# PowerSection.net
KiCad netlist of a schematic drawn in EAGLE
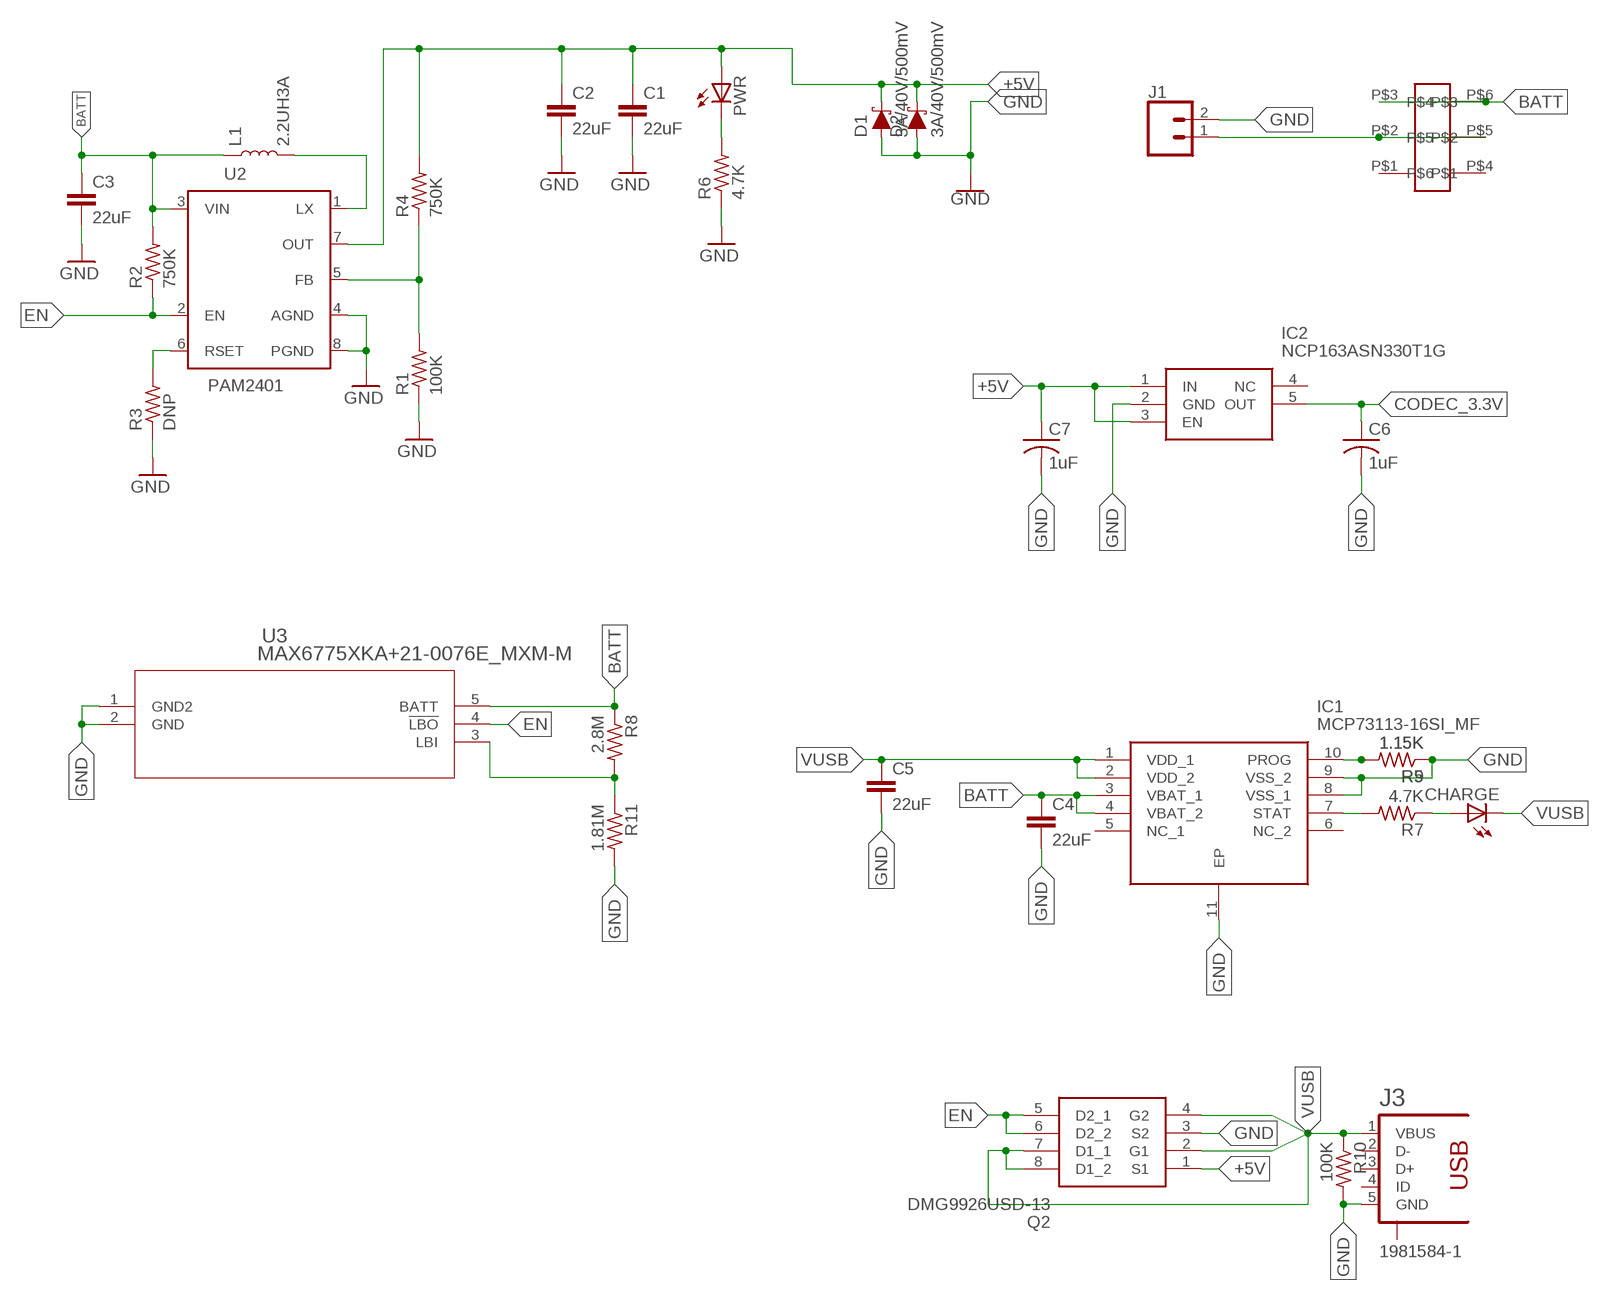
[diagram p0: schematic, sheet 1]

(export (version "E")
  (design (tool "Eeschema 10.0.6"))
  (components
    (comp (ref "C1")
      (value "22uF")
      (footprint "eagle-import:0805")
      (libsource (lib "eagle-import") (part "22UF-0805-6.3V-20%"))
    )
    (comp (ref "C2")
      (value "22uF")
      (footprint "eagle-import:0805")
      (libsource (lib "eagle-import") (part "22UF-0805-6.3V-20%"))
    )
    (comp (ref "C3")
      (value "22uF")
      (footprint "eagle-import:0805")
      (libsource (lib "eagle-import") (part "22UF-0805-6.3V-20%"))
    )
    (comp (ref "C4")
      (value "22uF")
      (footprint "eagle-import:0805")
      (libsource (lib "eagle-import") (part "22UF-0805-6.3V-20%"))
    )
    (comp (ref "C5")
      (value "22uF")
      (footprint "eagle-import:0805")
      (libsource (lib "eagle-import") (part "22UF-0805-6.3V-20%"))
    )
    (comp (ref "C6")
      (value "1uF")
      (footprint "eagle-import:C1206")
      (libsource (lib "eagle-import") (part "C-USC1206"))
    )
    (comp (ref "C7")
      (value "1uF")
      (footprint "eagle-import:C1206")
      (libsource (lib "eagle-import") (part "C-USC1206"))
    )
    (comp (ref "CHARGE")
      (value "LEDCHIPLED_0805")
      (footprint "eagle-import:CHIPLED_0805")
      (libsource (lib "eagle-import") (part "LEDCHIPLED_0805"))
    )
    (comp (ref "D1")
      (value "3A/40V/500mV")
      (footprint "eagle-import:SMA-DIODE")
      (libsource (lib "eagle-import") (part "DIODE-SCHOTTKY-B340A"))
    )
    (comp (ref "D2")
      (value "3A/40V/500mV")
      (footprint "eagle-import:SMA-DIODE")
      (libsource (lib "eagle-import") (part "DIODE-SCHOTTKY-B340A"))
    )
    (comp (ref "IC1")
      (value "MCP73113-16SI_MF")
      (footprint "eagle-import:SON50P300X300X100-11N")
      (fields
        (field (name "MANUFACTURER_PART_NUMBER") "MCP73113-16SI/MF")
        (field (name "MOUSER_PART_NUMBER") "579-MCP73113-16SI/MF")
      )
      (libsource (lib "eagle-import") (part "MCP73113-16SI_MF"))
    )
    (comp (ref "IC2")
      (value "NCP163ASN330T1G")
      (footprint "eagle-import:SOT95P280X145-5N")
      (fields (field (name "MOUSER_PART_NUMBER") "863-NCP163ASN330T1G"))
      (libsource (lib "eagle-import") (part "NCP163ASN330T1G"))
    )
    (comp (ref "J1")
      (value "CONN_02")
      (footprint "eagle-import:1X02")
      (libsource (lib "eagle-import") (part "CONN_02"))
    )
    (comp (ref "J3")
      (value "1981584-1")
      (footprint "eagle-import:1981584-1")
      (libsource (lib "eagle-import") (part "1981584-1"))
    )
    (comp (ref "L1")
      (value "2.2UH3A")
      (footprint "eagle-import:INDUCTOR_4X4MM")
      (libsource (lib "eagle-import") (part "INDUCTOR-IFSC1515AHER2R2M01"))
    )
    (comp (ref "PWR")
      (value "LEDCHIPLED_0805")
      (footprint "eagle-import:CHIPLED_0805")
      (libsource (lib "eagle-import") (part "LEDCHIPLED_0805"))
    )
    (comp (ref "Q2")
      (value "DMG9926USD-13")
      (footprint "eagle-import:SOIC127P600X175-8N")
      (fields (field (name "MOUSER_PART_NUMBER") "621-DMG9926USD-13"))
      (libsource (lib "eagle-import") (part "DMG9926USD-13"))
    )
    (comp (ref "R1")
      (value "100K")
      (footprint "eagle-import:M0805")
      (libsource (lib "eagle-import") (part "R-US_M0805"))
    )
    (comp (ref "R2")
      (value "750K")
      (footprint "eagle-import:M0805")
      (libsource (lib "eagle-import") (part "R-US_M0805"))
    )
    (comp (ref "R3")
      (value "DNP")
      (footprint "eagle-import:M0805")
      (libsource (lib "eagle-import") (part "R-US_M0805"))
    )
    (comp (ref "R4")
      (value "750K")
      (footprint "eagle-import:M0805")
      (libsource (lib "eagle-import") (part "R-US_M0805"))
    )
    (comp (ref "R5")
      (value "1.15K")
      (footprint "eagle-import:M0805")
      (libsource (lib "eagle-import") (part "R-US_M0805"))
    )
    (comp (ref "R6")
      (value "4.7K")
      (footprint "eagle-import:M0805")
      (libsource (lib "eagle-import") (part "R-US_M0805"))
    )
    (comp (ref "R7")
      (value "4.7K")
      (footprint "eagle-import:M0805")
      (libsource (lib "eagle-import") (part "R-US_M0805"))
    )
    (comp (ref "R8")
      (value "2.8M")
      (footprint "eagle-import:M0805")
      (libsource (lib "eagle-import") (part "R-US_M0805"))
    )
    (comp (ref "R9")
      (value "1.15K")
      (footprint "eagle-import:M0805")
      (libsource (lib "eagle-import") (part "R-US_M0805"))
    )
    (comp (ref "R10")
      (value "100K")
      (footprint "eagle-import:M0805")
      (libsource (lib "eagle-import") (part "R-US_M0805"))
    )
    (comp (ref "R11")
      (value "1.81M")
      (footprint "eagle-import:M0805")
      (libsource (lib "eagle-import") (part "R-US_M0805"))
    )
    (comp (ref "U$1")
      (value "JS202011JAQN")
      (footprint "eagle-import:JS202011JAQN")
      (libsource (lib "eagle-import") (part "JS202011JAQN"))
    )
    (comp (ref "U2")
      (value "PAM2401")
      (footprint "eagle-import:MSOP8")
      (libsource (lib "eagle-import") (part "PAM2401"))
    )
    (comp (ref "U3")
      (value "MAX6775XKA+21-0076E_MXM-M")
      (footprint "eagle-import:21-0076E_MXM-M")
      (fields (field (name "MANUFACTURER_PART_NUMBER") "MAX6775XKA+"))
      (libsource (lib "eagle-import") (part "MAX6775XKA+21-0076E_MXM-M"))
    )
  )
  (nets
    (net (code "1") (name "+5V") (class "Default")
      (node (ref "C1") (pin "1") (pinfunction "1_1") (pintype "passive"))
      (node (ref "C2") (pin "1") (pinfunction "1_1") (pintype "passive"))
      (node (ref "C7") (pin "1") (pinfunction "1_1") (pintype "passive"))
      (node (ref "D1") (pin "C") (pinfunction "C_C") (pintype "passive"))
      (node (ref "D2") (pin "C") (pinfunction "C_C") (pintype "passive"))
      (node (ref "IC2") (pin "1") (pinfunction "IN_1") (pintype "bidirectional"))
      (node (ref "IC2") (pin "3") (pinfunction "EN_3") (pintype "bidirectional"))
      (node (ref "PWR") (pin "A") (pinfunction "A_A") (pintype "passive"))
      (node (ref "Q2") (pin "1") (pinfunction "S1_1") (pintype "bidirectional"))
      (node (ref "R4") (pin "2") (pinfunction "2_2") (pintype "passive"))
      (node (ref "U2") (pin "7") (pinfunction "OUT_7") (pintype "bidirectional"))
    )
    (net (code "2") (name "BATT") (class "Default")
      (node (ref "C3") (pin "1") (pinfunction "1_1") (pintype "passive"))
      (node (ref "C4") (pin "1") (pinfunction "1_1") (pintype "passive"))
      (node (ref "IC1") (pin "3") (pinfunction "VBAT_1_3") (pintype "bidirectional"))
      (node (ref "IC1") (pin "4") (pinfunction "VBAT_2_4") (pintype "bidirectional"))
      (node (ref "L1") (pin "P$1") (pinfunction "1_P$1") (pintype "passive"))
      (node (ref "R2") (pin "2") (pinfunction "2_2") (pintype "passive"))
      (node (ref "R8") (pin "1") (pinfunction "1_1") (pintype "passive"))
      (node (ref "U$1") (pin "P$3") (pinfunction "P$3_P$3") (pintype "bidirectional"))
      (node (ref "U$1") (pin "P$6") (pinfunction "P$4_P$6") (pintype "bidirectional"))
      (node (ref "U2") (pin "3") (pinfunction "VIN_3") (pintype "bidirectional"))
      (node (ref "U3") (pin "5") (pinfunction "BATT_5") (pintype "input"))
    )
    (net (code "3") (name "CODEC_3.3V") (class "Default")
      (node (ref "C6") (pin "1") (pinfunction "1_1") (pintype "passive"))
      (node (ref "IC2") (pin "5") (pinfunction "OUT_5") (pintype "bidirectional"))
    )
    (net (code "4") (name "EN") (class "Default")
      (node (ref "Q2") (pin "5") (pinfunction "D2_1_5") (pintype "bidirectional"))
      (node (ref "Q2") (pin "6") (pinfunction "D2_2_6") (pintype "bidirectional"))
      (node (ref "R2") (pin "1") (pinfunction "1_1") (pintype "passive"))
      (node (ref "U2") (pin "2") (pinfunction "EN_2") (pintype "bidirectional"))
      (node (ref "U3") (pin "4") (pinfunction "~{LBO}_4") (pintype "output"))
    )
    (net (code "5") (name "GND") (class "Default")
      (node (ref "C1") (pin "2") (pinfunction "2_2") (pintype "passive"))
      (node (ref "C2") (pin "2") (pinfunction "2_2") (pintype "passive"))
      (node (ref "C3") (pin "2") (pinfunction "2_2") (pintype "passive"))
      (node (ref "C4") (pin "2") (pinfunction "2_2") (pintype "passive"))
      (node (ref "C5") (pin "2") (pinfunction "2_2") (pintype "passive"))
      (node (ref "C6") (pin "2") (pinfunction "2_2") (pintype "passive"))
      (node (ref "C7") (pin "2") (pinfunction "2_2") (pintype "passive"))
      (node (ref "D1") (pin "A") (pinfunction "A_A") (pintype "passive"))
      (node (ref "D2") (pin "A") (pinfunction "A_A") (pintype "passive"))
      (node (ref "IC1") (pin "11") (pinfunction "EP_11") (pintype "bidirectional"))
      (node (ref "IC1") (pin "8") (pinfunction "VSS_1_8") (pintype "bidirectional"))
      (node (ref "IC1") (pin "9") (pinfunction "VSS_2_9") (pintype "bidirectional"))
      (node (ref "IC2") (pin "2") (pinfunction "GND_2") (pintype "bidirectional"))
      (node (ref "J1") (pin "2") (pinfunction "2_2") (pintype "passive"))
      (node (ref "J3") (pin "5") (pinfunction "GND_5") (pintype "passive"))
      (node (ref "Q2") (pin "3") (pinfunction "S2_3") (pintype "bidirectional"))
      (node (ref "R1") (pin "1") (pinfunction "1_1") (pintype "passive"))
      (node (ref "R10") (pin "2") (pinfunction "2_2") (pintype "passive"))
      (node (ref "R11") (pin "2") (pinfunction "2_2") (pintype "passive"))
      (node (ref "R3") (pin "1") (pinfunction "1_1") (pintype "passive"))
      (node (ref "R5") (pin "1") (pinfunction "1_1") (pintype "passive"))
      (node (ref "R6") (pin "1") (pinfunction "1_1") (pintype "passive"))
      (node (ref "R9") (pin "1") (pinfunction "1_1") (pintype "passive"))
      (node (ref "U2") (pin "4") (pinfunction "AGND_4") (pintype "bidirectional"))
      (node (ref "U2") (pin "8") (pinfunction "PGND_8") (pintype "bidirectional"))
      (node (ref "U3") (pin "1") (pinfunction "GND2_1") (pintype "power_in"))
      (node (ref "U3") (pin "2") (pinfunction "GND_2") (pintype "power_in"))
    )
    (net (code "6") (name "Net-(CHARGE-PadA)") (class "Default")
      (node (ref "CHARGE") (pin "A") (pinfunction "A_A") (pintype "passive"))
      (node (ref "R7") (pin "1") (pinfunction "1_1") (pintype "passive"))
    )
    (net (code "7") (name "Net-(IC1-PROG)") (class "Default")
      (node (ref "IC1") (pin "10") (pinfunction "PROG_10") (pintype "bidirectional"))
      (node (ref "R5") (pin "2") (pinfunction "2_2") (pintype "passive"))
      (node (ref "R9") (pin "2") (pinfunction "2_2") (pintype "passive"))
    )
    (net (code "8") (name "Net-(IC1-STAT)") (class "Default")
      (node (ref "IC1") (pin "7") (pinfunction "STAT_7") (pintype "bidirectional"))
      (node (ref "R7") (pin "2") (pinfunction "2_2") (pintype "passive"))
    )
    (net (code "9") (name "Net-(J1-Pad1)") (class "Default")
      (node (ref "J1") (pin "1") (pinfunction "1_1") (pintype "passive"))
      (node (ref "U$1") (pin "P$2") (pinfunction "P$2_P$2") (pintype "bidirectional"))
      (node (ref "U$1") (pin "P$5") (pinfunction "P$5_P$5") (pintype "bidirectional"))
    )
    (net (code "10") (name "Net-(L1-2)") (class "Default")
      (node (ref "L1") (pin "P$2") (pinfunction "2_P$2") (pintype "passive"))
      (node (ref "U2") (pin "1") (pinfunction "LX_1") (pintype "bidirectional"))
    )
    (net (code "11") (name "Net-(PWR-PadC)") (class "Default")
      (node (ref "PWR") (pin "C") (pinfunction "C_C") (pintype "passive"))
      (node (ref "R6") (pin "2") (pinfunction "2_2") (pintype "passive"))
    )
    (net (code "12") (name "Net-(U2-FB)") (class "Default")
      (node (ref "R1") (pin "2") (pinfunction "2_2") (pintype "passive"))
      (node (ref "R4") (pin "1") (pinfunction "1_1") (pintype "passive"))
      (node (ref "U2") (pin "5") (pinfunction "FB_5") (pintype "bidirectional"))
    )
    (net (code "13") (name "Net-(U2-RSET)") (class "Default")
      (node (ref "R3") (pin "2") (pinfunction "2_2") (pintype "passive"))
      (node (ref "U2") (pin "6") (pinfunction "RSET_6") (pintype "bidirectional"))
    )
    (net (code "14") (name "Net-(U3-LBI)") (class "Default")
      (node (ref "R11") (pin "1") (pinfunction "1_1") (pintype "passive"))
      (node (ref "R8") (pin "2") (pinfunction "2_2") (pintype "passive"))
      (node (ref "U3") (pin "3") (pinfunction "LBI_3") (pintype "input"))
    )
    (net (code "15") (name "VUSB") (class "Default")
      (node (ref "C5") (pin "1") (pinfunction "1_1") (pintype "passive"))
      (node (ref "CHARGE") (pin "C") (pinfunction "C_C") (pintype "passive"))
      (node (ref "IC1") (pin "1") (pinfunction "VDD_1_1") (pintype "bidirectional"))
      (node (ref "IC1") (pin "2") (pinfunction "VDD_2_2") (pintype "bidirectional"))
      (node (ref "J3") (pin "1") (pinfunction "VBUS_1") (pintype "passive"))
      (node (ref "Q2") (pin "2") (pinfunction "G1_2") (pintype "bidirectional"))
      (node (ref "Q2") (pin "4") (pinfunction "G2_4") (pintype "bidirectional"))
      (node (ref "Q2") (pin "7") (pinfunction "D1_1_7") (pintype "bidirectional"))
      (node (ref "Q2") (pin "8") (pinfunction "D1_2_8") (pintype "bidirectional"))
      (node (ref "R10") (pin "1") (pinfunction "1_1") (pintype "passive"))
    )
    (net (code "16") (name "unconnected-(IC1-NC_1-Pad5)") (class "Default")
      (node (ref "IC1") (pin "5") (pinfunction "NC_1_5") (pintype "bidirectional"))
    )
    (net (code "17") (name "unconnected-(IC1-NC_2-Pad6)") (class "Default")
      (node (ref "IC1") (pin "6") (pinfunction "NC_2_6") (pintype "bidirectional"))
    )
    (net (code "18") (name "unconnected-(IC2-NC-Pad4)") (class "Default")
      (node (ref "IC2") (pin "4") (pinfunction "NC_4") (pintype "no_connect"))
    )
    (net (code "19") (name "unconnected-(J3-D+-Pad3)") (class "Default")
      (node (ref "J3") (pin "3") (pinfunction "D+_3") (pintype "passive"))
    )
    (net (code "20") (name "unconnected-(J3-D--Pad2)") (class "Default")
      (node (ref "J3") (pin "2") (pinfunction "D-_2") (pintype "passive"))
    )
    (net (code "21") (name "unconnected-(J3-ID-Pad4)") (class "Default")
      (node (ref "J3") (pin "4") (pinfunction "ID_4") (pintype "passive"))
    )
    (net (code "22") (name "unconnected-(J3-PadS1)") (class "Default")
      (node (ref "J3") (pin "S1") (pinfunction "S1_S1") (pintype "passive"))
    )
    (net (code "23") (name "unconnected-(U$1-P$6-PadP$4)") (class "Default")
      (node (ref "U$1") (pin "P$4") (pinfunction "P$6_P$4") (pintype "bidirectional"))
    )
    (net (code "24") (name "unconnected-(U$1-PadP$1)") (class "Default")
      (node (ref "U$1") (pin "P$1") (pinfunction "P$1_P$1") (pintype "bidirectional"))
    )
  )
)
